# 1_P1_schdoc.net
KiCad netlist of a schematic drawn in Altium Designer
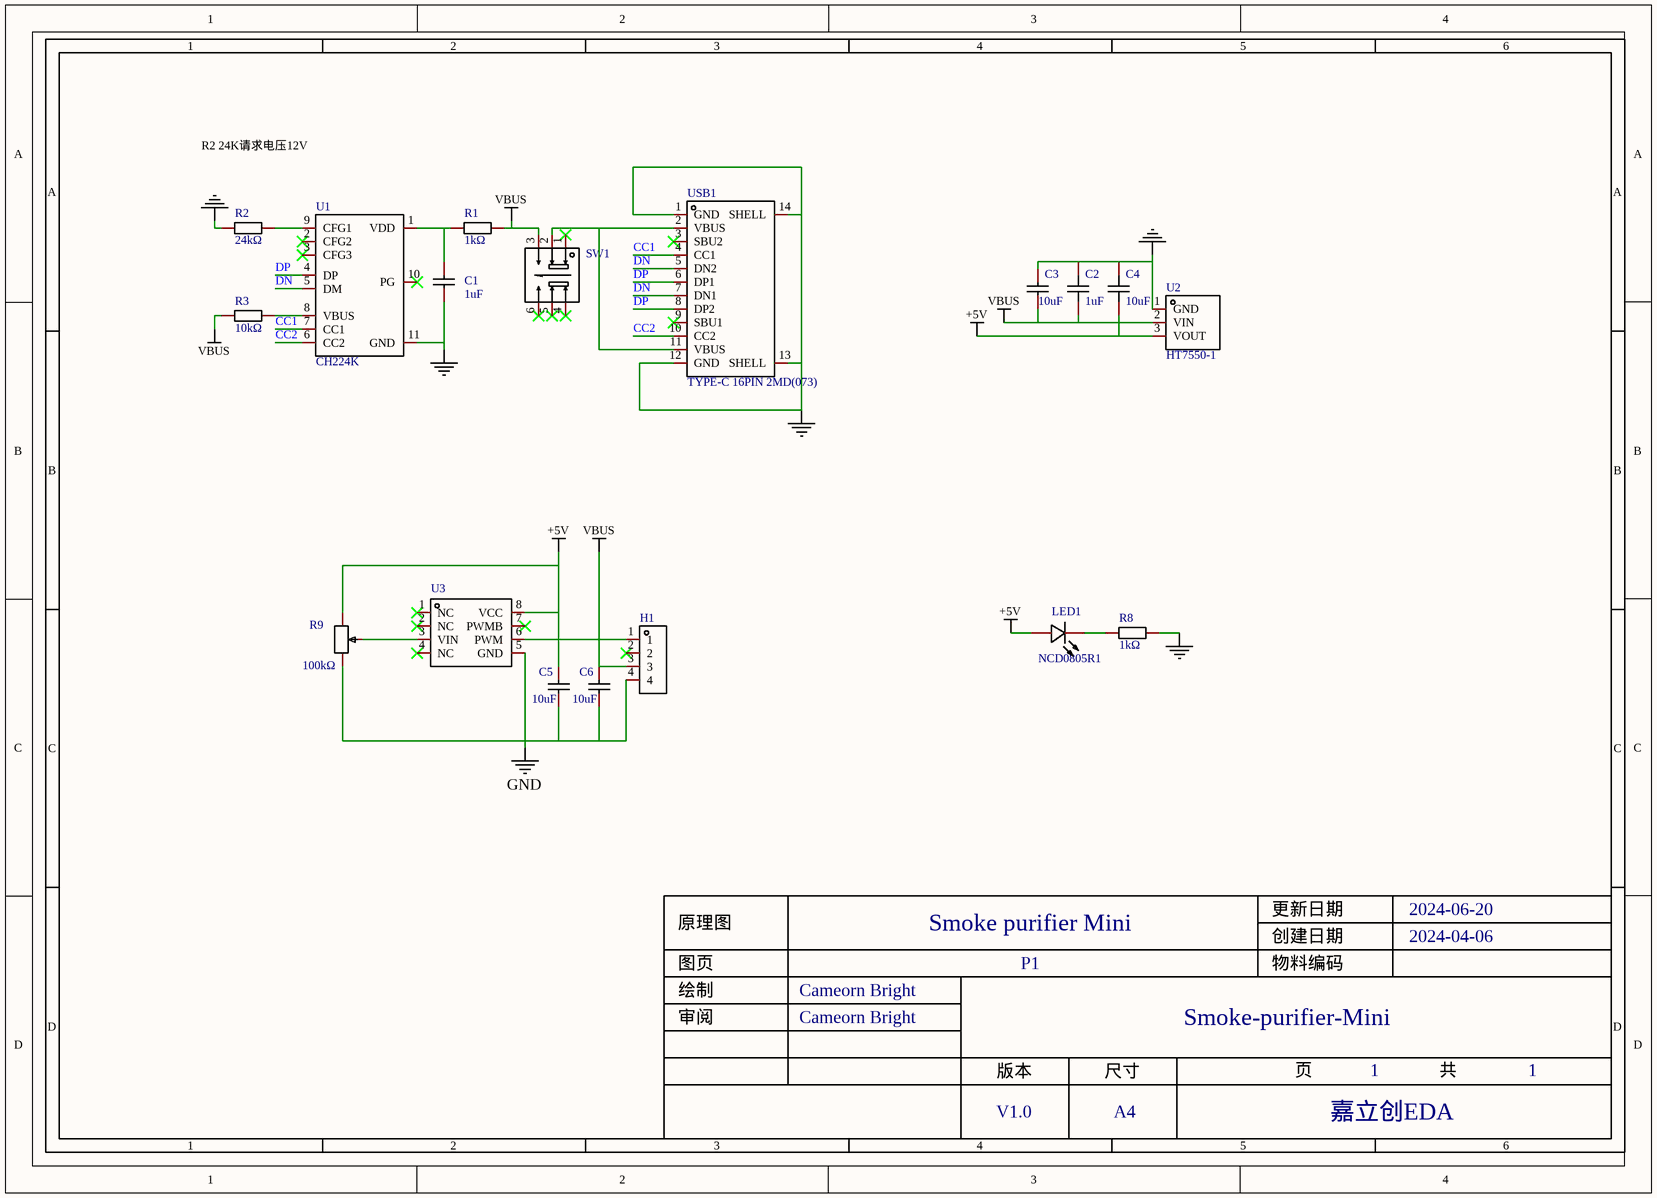
[diagram p0: 1_P1.schdoc.schdoc]

(export (version "E")
  (design (tool "Eeschema 10.0.6"))
  (components
    (comp (ref "C1")
      (value "1uF")
      (fields
        (field (name "NAME") "1uF")
        (field (name "MANUFACTURER PART") "CL10A105KB8NNNC")
        (field (name "MANUFACTURER") "SAMSUNG(三星)")
        (field (name "TOLERANCE") "±10%")
      )
      (libsource (lib "altium-import") (part "root_1_CL10A105KB8NNNC_"))
    )
    (comp (ref "C2")
      (value "1uF")
      (fields
        (field (name "NAME") "1uF")
        (field (name "MANUFACTURER") "muRata(村田)")
        (field (name "MANUFACTURER PART") "GRM21BR61H106KE43L")
        (field (name "TOLERANCE") "±10%")
      )
      (libsource (lib "altium-import") (part "root_1_GRM21BR61H106KE43L_"))
    )
    (comp (ref "C3")
      (value "10uF")
      (fields
        (field (name "NAME") "10uF")
        (field (name "MANUFACTURER PART") "CL21B105KBFNNNE")
        (field (name "MANUFACTURER") "SAMSUNG(三星)")
        (field (name "TOLERANCE") "±10%")
      )
      (libsource (lib "altium-import") (part "root_1_CL21B105KBFNNNE_"))
    )
    (comp (ref "C4")
      (value "10uF")
      (fields
        (field (name "NAME") "10uF")
        (field (name "MANUFACTURER") "muRata(村田)")
        (field (name "MANUFACTURER PART") "GRM21BR61H106KE43L")
        (field (name "TOLERANCE") "±10%")
      )
      (libsource (lib "altium-import") (part "root_1_GRM21BR61H106KE43L_"))
    )
    (comp (ref "C5")
      (value "10uF")
      (fields
        (field (name "MANUFACTURER") "muRata(村田)")
        (field (name "MANUFACTURER PART") "GRM188R6YA106MA73D")
        (field (name "TOLERANCE") "±20%")
      )
      (libsource (lib "altium-import") (part "root_1_GRM188R6YA106MA73D_"))
    )
    (comp (ref "C6")
      (value "10uF")
      (fields
        (field (name "MANUFACTURER") "muRata(村田)")
        (field (name "MANUFACTURER PART") "GRM188R6YA106MA73D")
        (field (name "TOLERANCE") "±20%")
      )
      (libsource (lib "altium-import") (part "root_1_GRM188R6YA106MA73D_"))
    )
    (comp (ref "H1")
      (value "HDR-F_2.54_1x4P")
      (fields (field (name "MANUFACTURER") "BOOMELE(博穆精密)") (field (name "MANUFACTURER PART") "2.54-1*4P母"))
      (libsource (lib "altium-import") (part "root_0_HDR-F_2.54_1x4P_"))
    )
    (comp (ref "LED1")
      (value "NCD0805R1")
      (fields (field (name "NAME") "NCD0805R1") (field (name "MANUFACTURER") "国星光电"))
      (libsource (lib "altium-import") (part "root_2_NCD0805R1_"))
    )
    (comp (ref "R1")
      (value "1kΩ")
      (fields
        (field (name "NAME") "1kΩ")
        (field (name "MANUFACTURER") "YAGEO(国巨)")
        (field (name "MANUFACTURER PART") "RC0603FR-071KL")
        (field (name "TOLERANCE") "±1%")
      )
      (libsource (lib "altium-import") (part "root_0_RC0603FR-071KL_"))
    )
    (comp (ref "R2")
      (value "24kΩ")
      (fields
        (field (name "NAME") "24kΩ")
        (field (name "MANUFACTURER") "UNI-ROYAL(厚声)")
        (field (name "MANUFACTURER PART") "0603WAF2402T5E")
        (field (name "TOLERANCE") "±1%")
      )
      (libsource (lib "altium-import") (part "root_2_0603WAF2402T5E_"))
    )
    (comp (ref "R3")
      (value "10kΩ")
      (fields
        (field (name "NAME") "10kΩ")
        (field (name "MANUFACTURER") "UNI-ROYAL(厚声)")
        (field (name "MANUFACTURER PART") "0603WAF1002T5E")
        (field (name "TOLERANCE") "±1%")
      )
      (libsource (lib "altium-import") (part "root_0_0603WAF1002T5E_"))
    )
    (comp (ref "R8")
      (value "1kΩ")
      (fields
        (field (name "NAME") "1kΩ")
        (field (name "MANUFACTURER") "YAGEO(国巨)")
        (field (name "MANUFACTURER PART") "RC0603FR-071KL")
        (field (name "TOLERANCE") "±1%")
      )
      (libsource (lib "altium-import") (part "root_0_RC0603FR-071KL_"))
    )
    (comp (ref "R9")
      (value "100kΩ")
      (fields
        (field (name "NAME") "100kΩ")
        (field (name "MANUFACTURER") "BOURNS")
        (field (name "MANUFACTURER PART") "3296W-1-104LF")
        (field (name "TOLERANCE") "±10%")
      )
      (libsource (lib "altium-import") (part "root_2_3296W-1-104LF_"))
    )
    (comp (ref "SW1")
      (value "PS-5850A-6PL")
      (description "电路结构:双刀双掷;自锁/无锁:自锁;安装方式:直插;触点电流:500mA;额定电压 (AC):-;额定电压 (DC):30V;带灯:-;作用力:-;机械寿命:10万次;")
      (fields (field (name "MANUFACTURER") "G-Switch(品赞)"))
      (libsource (lib "altium-import") (part "root_3_PS-5850A-6PL_"))
    )
    (comp (ref "U1")
      (value "CH224K")
      (description "应用功能:USB充电芯片;")
      (fields (field (name "NAME") "CH224K") (field (name "MANUFACTURER") "WCH(南京沁恒)"))
      (libsource (lib "altium-import") (part "root_0_CH224K_"))
    )
    (comp (ref "U2")
      (value "HT7550-1")
      (description "输出类型:固定;最大输入电压:30V;输出电压:5V;最大输出电流:100mA;电源纹波抑制比(PSRR):-;输出极性:正极;")
      (fields (field (name "NAME") "HT7550-1") (field (name "MANUFACTURER") "UMW(友台半导体)"))
      (libsource (lib "altium-import") (part "root_0_HT7550-1_C347189_"))
    )
    (comp (ref "U3")
      (value "GP9101-F20K-L2H1-SW")
      (description "GP9101 0-VCC转PWM 20KHz L2H1")
      (fields (field (name "MANUFACTURER") "Guestgood(客益)"))
      (libsource (lib "altium-import") (part "root_0_GP9101-F20K-L2H1-SW_"))
    )
    (comp (ref "USB1")
      (value "TYPE-C 16PIN 2MD(073)")
      (description "连接器类型:Type-C;标准:-;公母:母;端口数量:1;触点数量:16P;安装方式:卧贴;额定电流 - 电源:5A;工作温度范围:-25℃~+85℃;")
      (fields (field (name "NAME") "TYPE-C 16PIN 2MD(073)") (field (name "MANUFACTURER") "SHOU HAN(首韩)"))
      (libsource (lib "altium-import") (part "root_0_TYPE-C 16PIN 2MD(073)_"))
    )
  )
  (nets
    (net (code "1") (name "+5V") (class "Default")
      (node (ref "C4") (pin "1") (pinfunction "1_1") (pintype "passive"))
      (node (ref "C5") (pin "2") (pinfunction "2_2") (pintype "passive"))
      (node (ref "LED1") (pin "1") (pinfunction "+_1") (pintype "passive"))
      (node (ref "R9") (pin "3") (pinfunction "3_3") (pintype "passive"))
      (node (ref "U2") (pin "3") (pinfunction "VOUT_3") (pintype "passive"))
      (node (ref "U3") (pin "8") (pinfunction "VCC_8") (pintype "passive"))
    )
    (net (code "2") (name "/CC1") (class "Default")
      (node (ref "U1") (pin "7") (pinfunction "CC1_7") (pintype "passive"))
      (node (ref "USB1") (pin "4") (pinfunction "CC1_4") (pintype "passive"))
    )
    (net (code "3") (name "/CC2") (class "Default")
      (node (ref "U1") (pin "6") (pinfunction "CC2_6") (pintype "passive"))
      (node (ref "USB1") (pin "10") (pinfunction "CC2_10") (pintype "passive"))
    )
    (net (code "4") (name "/DN") (class "Default")
      (node (ref "U1") (pin "5") (pinfunction "DM_5") (pintype "passive"))
      (node (ref "USB1") (pin "5") (pinfunction "DN2_5") (pintype "passive"))
      (node (ref "USB1") (pin "7") (pinfunction "DN1_7") (pintype "passive"))
    )
    (net (code "5") (name "/DP") (class "Default")
      (node (ref "U1") (pin "4") (pinfunction "DP_4") (pintype "passive"))
      (node (ref "USB1") (pin "6") (pinfunction "DP1_6") (pintype "passive"))
      (node (ref "USB1") (pin "8") (pinfunction "DP2_8") (pintype "passive"))
    )
    (net (code "6") (name "GND") (class "Default")
      (node (ref "C1") (pin "1") (pinfunction "1_1") (pintype "passive"))
      (node (ref "C2") (pin "2") (pinfunction "2_2") (pintype "passive"))
      (node (ref "C3") (pin "2") (pinfunction "2_2") (pintype "passive"))
      (node (ref "C4") (pin "2") (pinfunction "2_2") (pintype "passive"))
      (node (ref "C5") (pin "1") (pinfunction "1_1") (pintype "passive"))
      (node (ref "C6") (pin "1") (pinfunction "1_1") (pintype "passive"))
      (node (ref "H1") (pin "4") (pinfunction "4_4") (pintype "passive"))
      (node (ref "R2") (pin "2") (pinfunction "2_2") (pintype "passive"))
      (node (ref "R8") (pin "2") (pinfunction "2_2") (pintype "passive"))
      (node (ref "R9") (pin "1") (pinfunction "1_1") (pintype "passive"))
      (node (ref "U1") (pin "11") (pinfunction "GND_11") (pintype "passive"))
      (node (ref "U2") (pin "1") (pinfunction "GND_1") (pintype "passive"))
      (node (ref "U3") (pin "5") (pinfunction "GND_5") (pintype "passive"))
      (node (ref "USB1") (pin "1") (pinfunction "GND_1") (pintype "passive"))
      (node (ref "USB1") (pin "12") (pinfunction "GND_12") (pintype "passive"))
      (node (ref "USB1") (pin "13") (pinfunction "SHELL_13") (pintype "passive"))
      (node (ref "USB1") (pin "14") (pinfunction "SHELL_14") (pintype "passive"))
    )
    (net (code "7") (name "Net-(LED1--)") (class "Default")
      (node (ref "LED1") (pin "2") (pinfunction "-_2") (pintype "passive"))
      (node (ref "R8") (pin "1") (pinfunction "1_1") (pintype "passive"))
    )
    (net (code "8") (name "Net-(SW1-Pad2)") (class "Default")
      (node (ref "SW1") (pin "2") (pinfunction "2_2") (pintype "passive"))
      (node (ref "USB1") (pin "11") (pinfunction "VBUS_11") (pintype "passive"))
      (node (ref "USB1") (pin "2") (pinfunction "VBUS_2") (pintype "passive"))
    )
    (net (code "9") (name "Net-(U1-CFG1)") (class "Default")
      (node (ref "R2") (pin "1") (pinfunction "1_1") (pintype "passive"))
      (node (ref "U1") (pin "9") (pinfunction "CFG1_9") (pintype "passive"))
    )
    (net (code "10") (name "Net-(U1-VBUS)") (class "Default")
      (node (ref "R3") (pin "2") (pinfunction "2_2") (pintype "passive"))
      (node (ref "U1") (pin "8") (pinfunction "VBUS_8") (pintype "passive"))
    )
    (net (code "11") (name "Net-(U1-VDD)") (class "Default")
      (node (ref "C1") (pin "2") (pinfunction "2_2") (pintype "passive"))
      (node (ref "R1") (pin "1") (pinfunction "1_1") (pintype "passive"))
      (node (ref "U1") (pin "1") (pinfunction "VDD_1") (pintype "passive"))
    )
    (net (code "12") (name "Net-(U3-PWM)") (class "Default")
      (node (ref "H1") (pin "1") (pinfunction "1_1") (pintype "passive"))
      (node (ref "U3") (pin "6") (pinfunction "PWM_6") (pintype "passive"))
    )
    (net (code "13") (name "Net-(U3-VIN)") (class "Default")
      (node (ref "R9") (pin "2") (pinfunction "2_2") (pintype "passive"))
      (node (ref "U3") (pin "3") (pinfunction "VIN_3") (pintype "passive"))
    )
    (net (code "14") (name "VBUS") (class "Default")
      (node (ref "C2") (pin "1") (pinfunction "1_1") (pintype "passive"))
      (node (ref "C3") (pin "1") (pinfunction "1_1") (pintype "passive"))
      (node (ref "C6") (pin "2") (pinfunction "2_2") (pintype "passive"))
      (node (ref "H1") (pin "3") (pinfunction "3_3") (pintype "passive"))
      (node (ref "R1") (pin "2") (pinfunction "2_2") (pintype "passive"))
      (node (ref "R3") (pin "1") (pinfunction "1_1") (pintype "passive"))
      (node (ref "SW1") (pin "3") (pinfunction "3_3") (pintype "passive"))
      (node (ref "U2") (pin "2") (pinfunction "VIN_2") (pintype "passive"))
    )
    (net (code "15") (name "unconnected-(H1-Pad2)") (class "Default")
      (node (ref "H1") (pin "2") (pinfunction "2_2") (pintype "passive+no_connect"))
    )
    (net (code "16") (name "unconnected-(SW1-Pad1)") (class "Default")
      (node (ref "SW1") (pin "1") (pinfunction "1_1") (pintype "passive+no_connect"))
    )
    (net (code "17") (name "unconnected-(SW1-Pad4)") (class "Default")
      (node (ref "SW1") (pin "4") (pinfunction "4_4") (pintype "passive+no_connect"))
    )
    (net (code "18") (name "unconnected-(SW1-Pad5)") (class "Default")
      (node (ref "SW1") (pin "5") (pinfunction "5_5") (pintype "passive+no_connect"))
    )
    (net (code "19") (name "unconnected-(SW1-Pad6)") (class "Default")
      (node (ref "SW1") (pin "6") (pinfunction "6_6") (pintype "passive+no_connect"))
    )
    (net (code "20") (name "unconnected-(U1-CFG2-Pad2)") (class "Default")
      (node (ref "U1") (pin "2") (pinfunction "CFG2_2") (pintype "passive+no_connect"))
    )
    (net (code "21") (name "unconnected-(U1-CFG3-Pad3)") (class "Default")
      (node (ref "U1") (pin "3") (pinfunction "CFG3_3") (pintype "passive+no_connect"))
    )
    (net (code "22") (name "unconnected-(U1-PG-Pad10)") (class "Default")
      (node (ref "U1") (pin "10") (pinfunction "PG_10") (pintype "passive+no_connect"))
    )
    (net (code "23") (name "unconnected-(U3-NC-Pad1)") (class "Default")
      (node (ref "U3") (pin "1") (pinfunction "NC_1") (pintype "passive+no_connect"))
    )
    (net (code "24") (name "unconnected-(U3-NC-Pad2)") (class "Default")
      (node (ref "U3") (pin "2") (pinfunction "NC_2") (pintype "passive+no_connect"))
    )
    (net (code "25") (name "unconnected-(U3-NC-Pad4)") (class "Default")
      (node (ref "U3") (pin "4") (pinfunction "NC_4") (pintype "passive+no_connect"))
    )
    (net (code "26") (name "unconnected-(U3-PWMB-Pad7)") (class "Default")
      (node (ref "U3") (pin "7") (pinfunction "PWMB_7") (pintype "passive+no_connect"))
    )
    (net (code "27") (name "unconnected-(USB1-SBU1-Pad9)") (class "Default")
      (node (ref "USB1") (pin "9") (pinfunction "SBU1_9") (pintype "passive+no_connect"))
    )
    (net (code "28") (name "unconnected-(USB1-SBU2-Pad3)") (class "Default")
      (node (ref "USB1") (pin "3") (pinfunction "SBU2_3") (pintype "passive+no_connect"))
    )
  )
)
